# vmuzero_SEPS525_V2.net
KiCad netlist of a schematic drawn in EAGLE
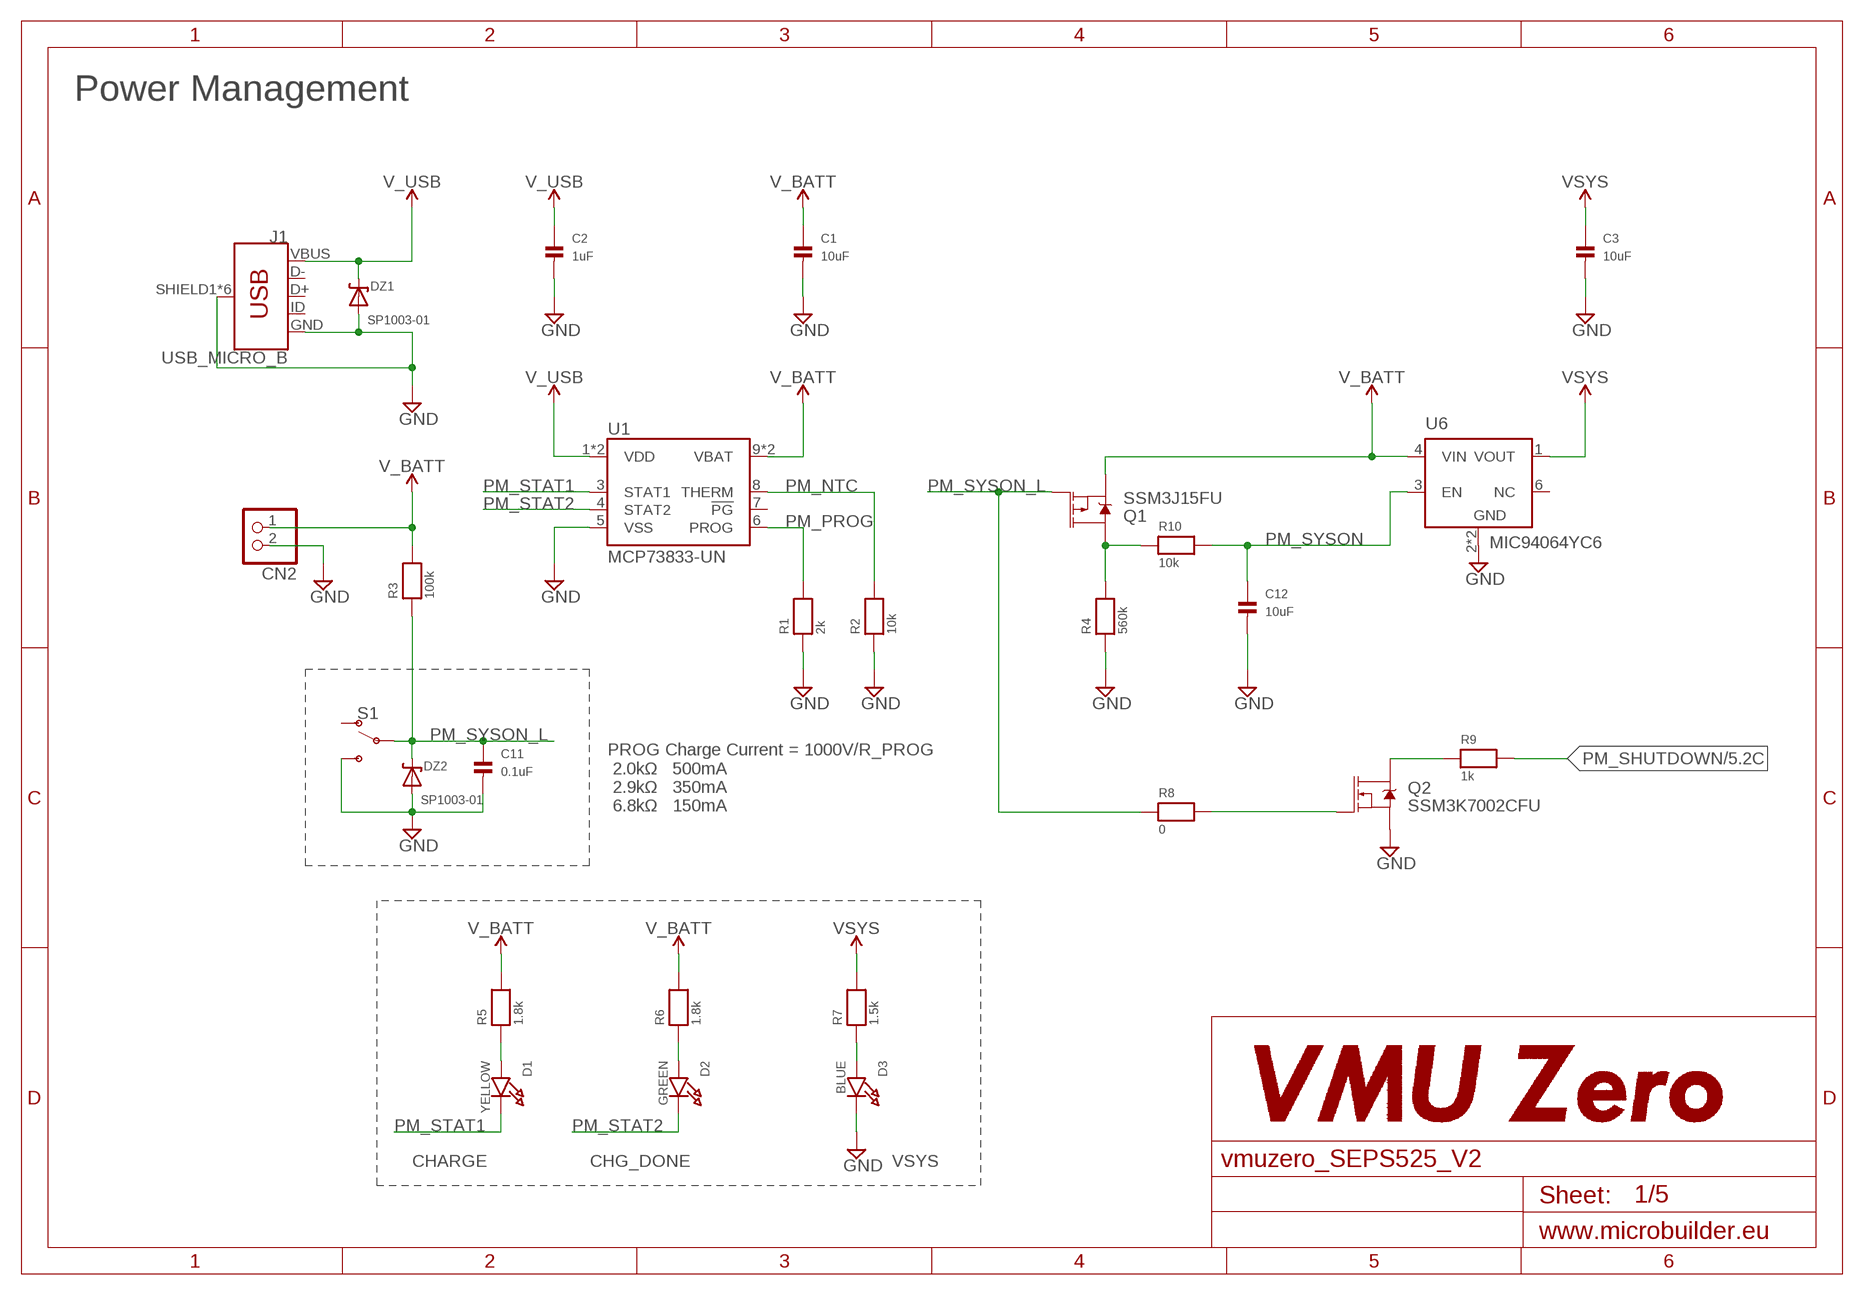
[diagram p0: schematic, sheet 1]
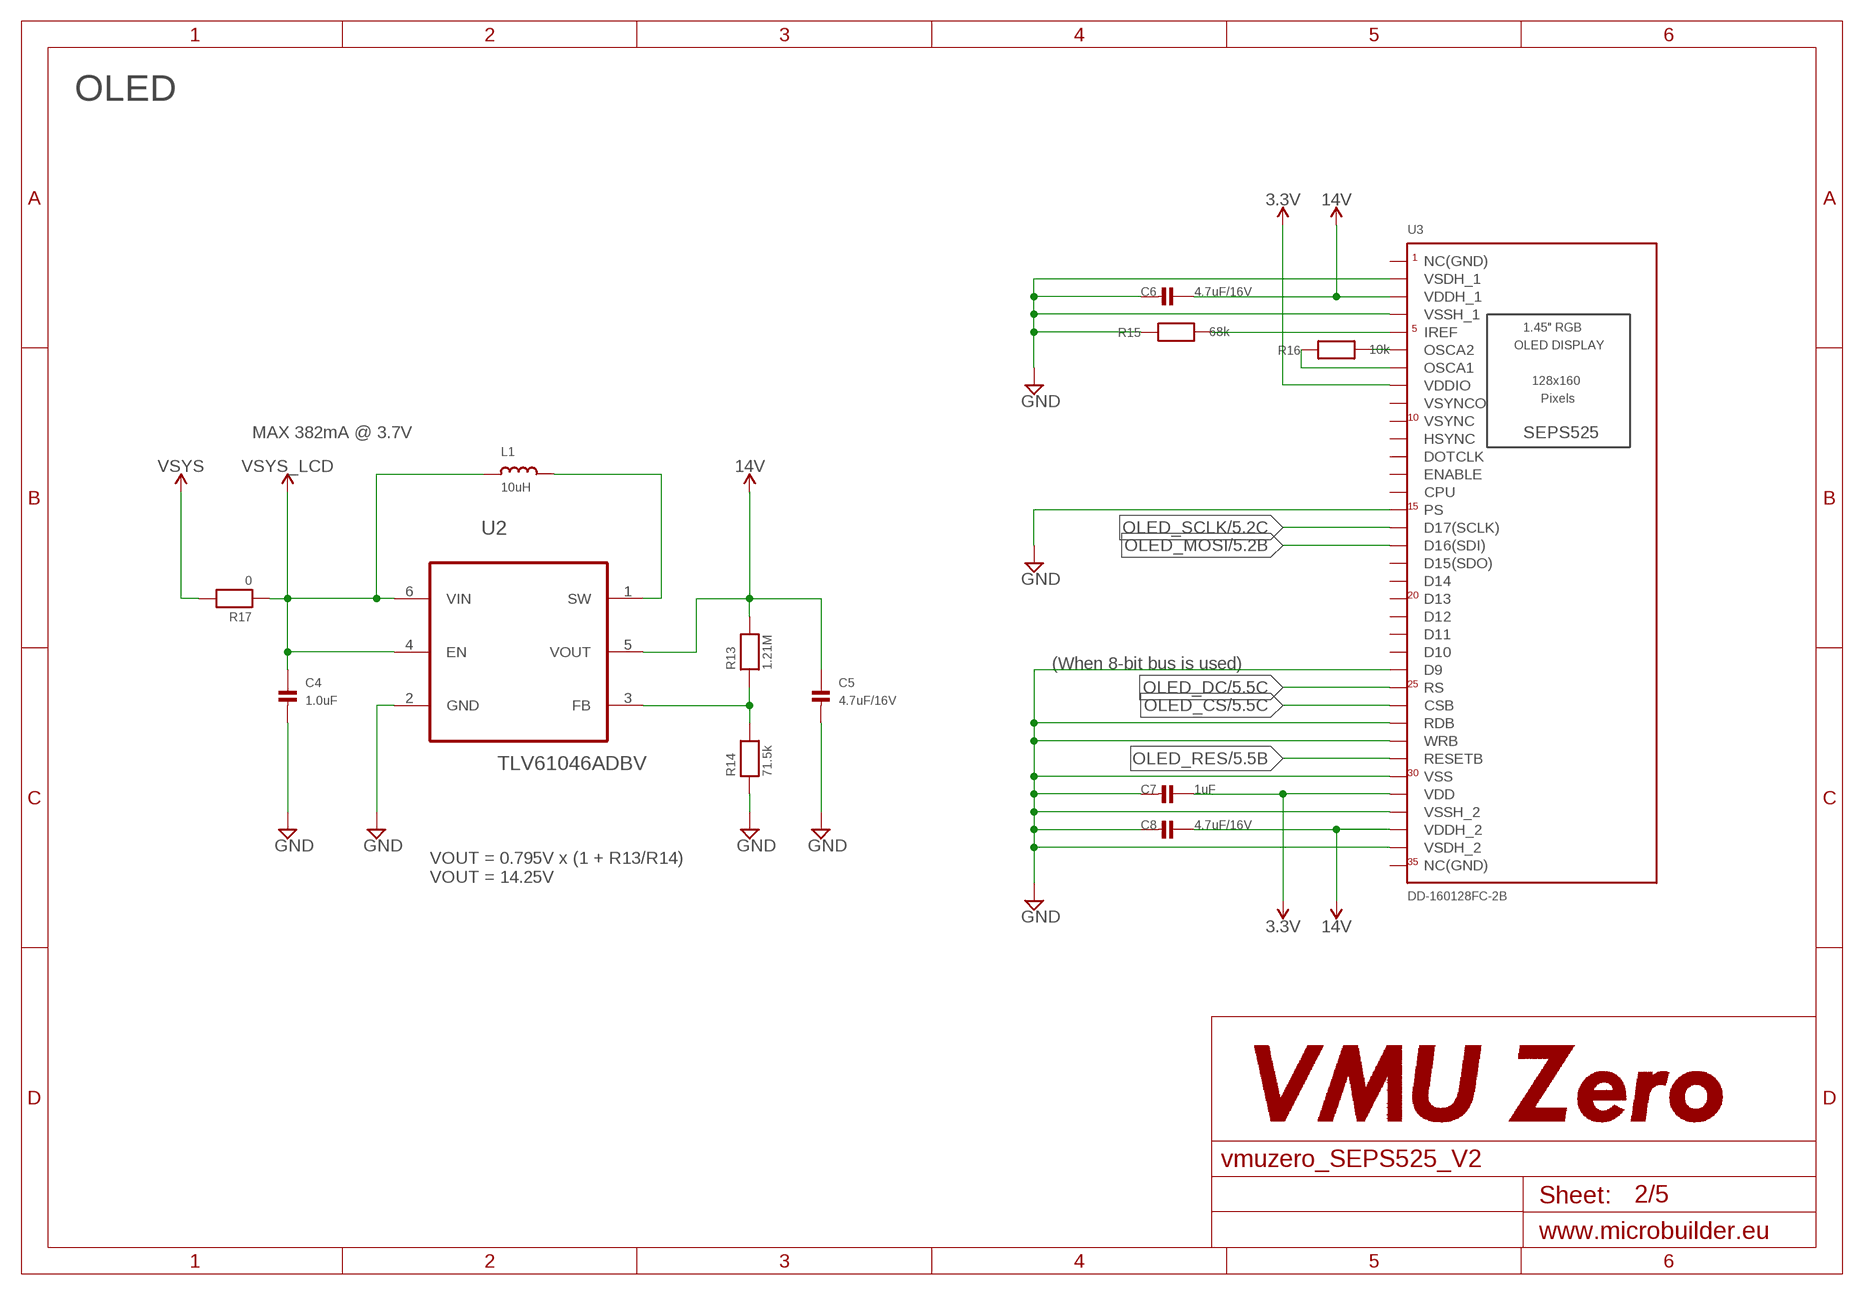
[diagram p1: schematic, sheet 2]
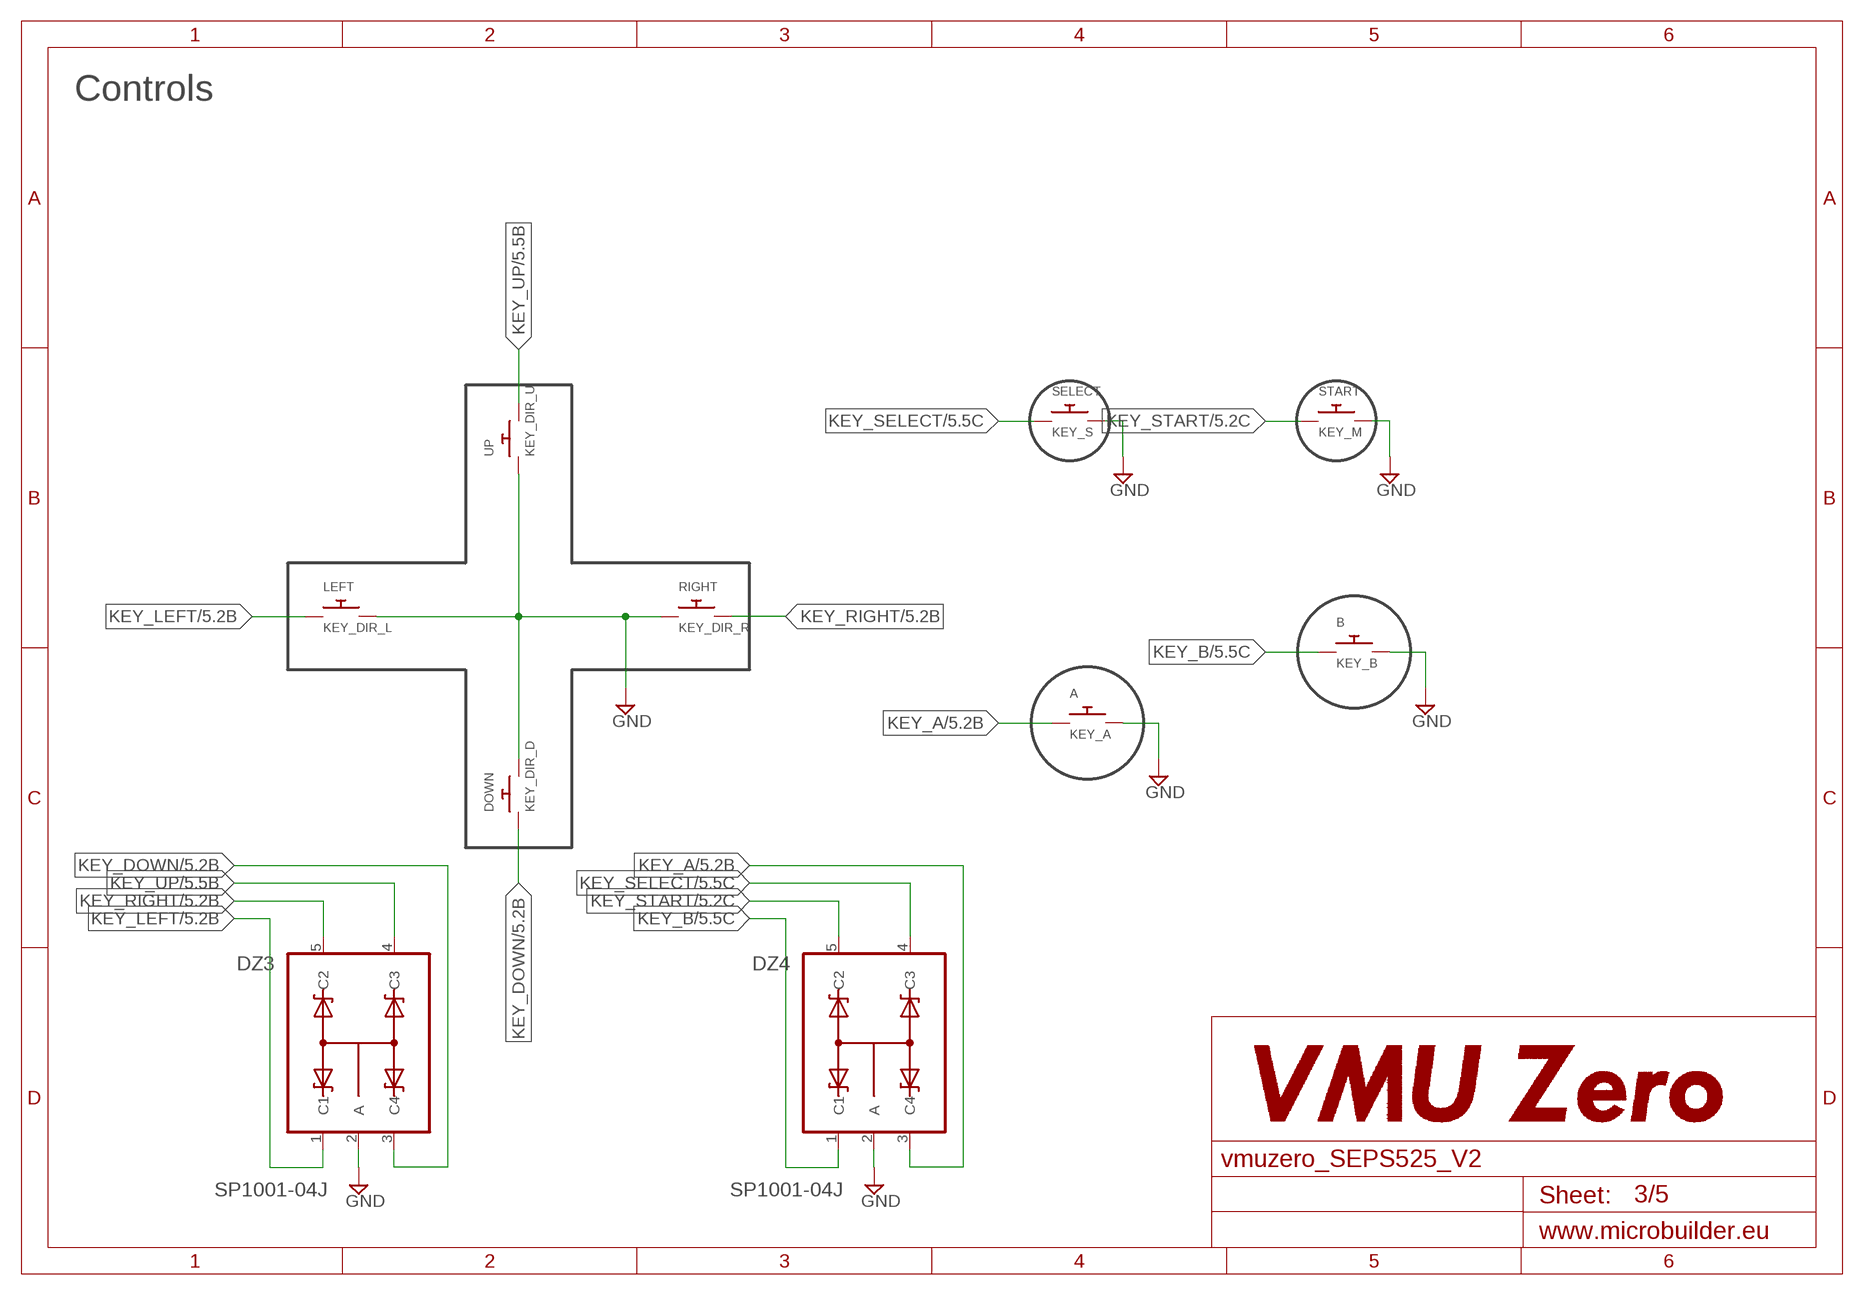
[diagram p2: schematic, sheet 3]
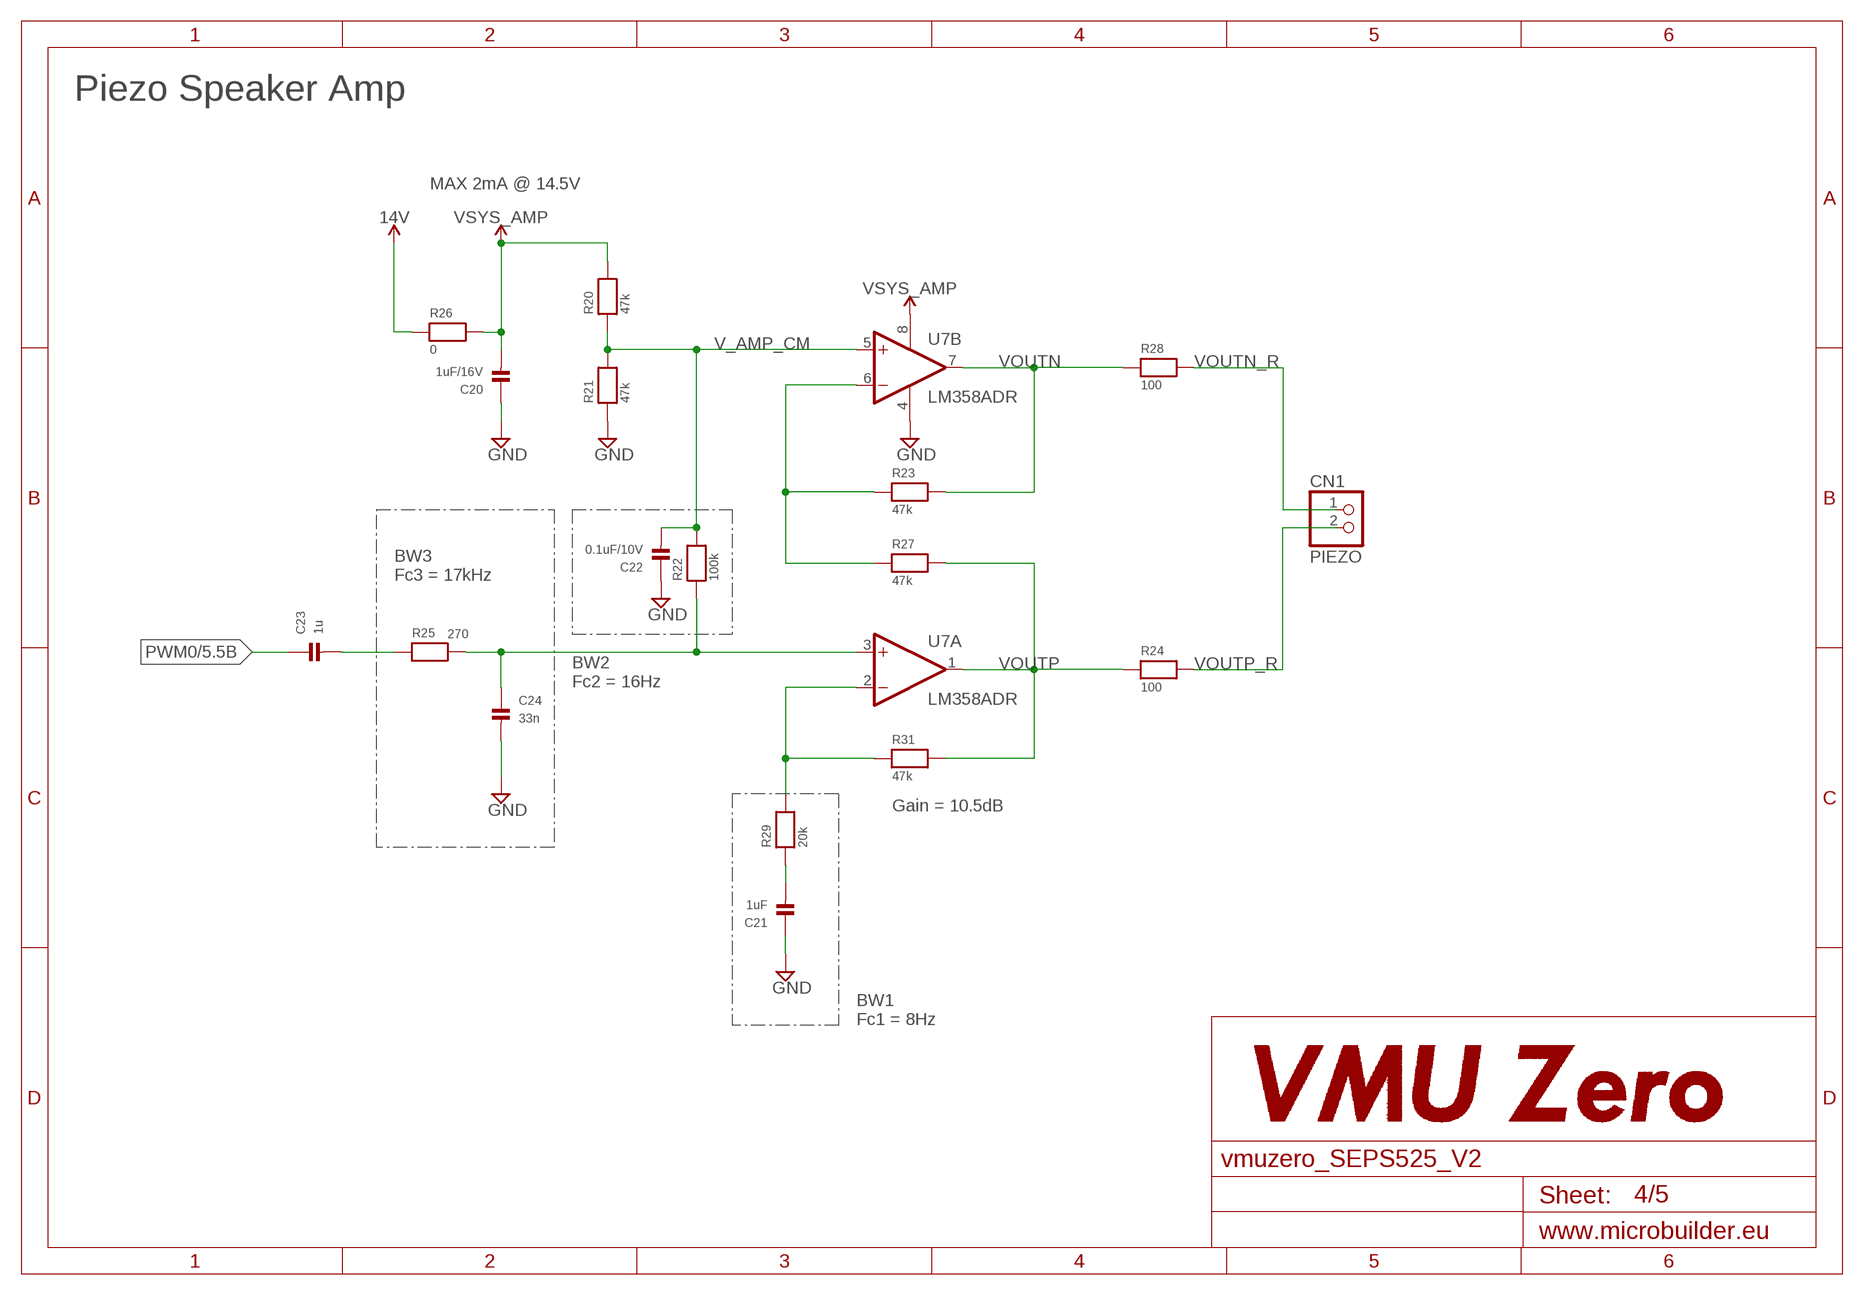
[diagram p3: schematic, sheet 4]
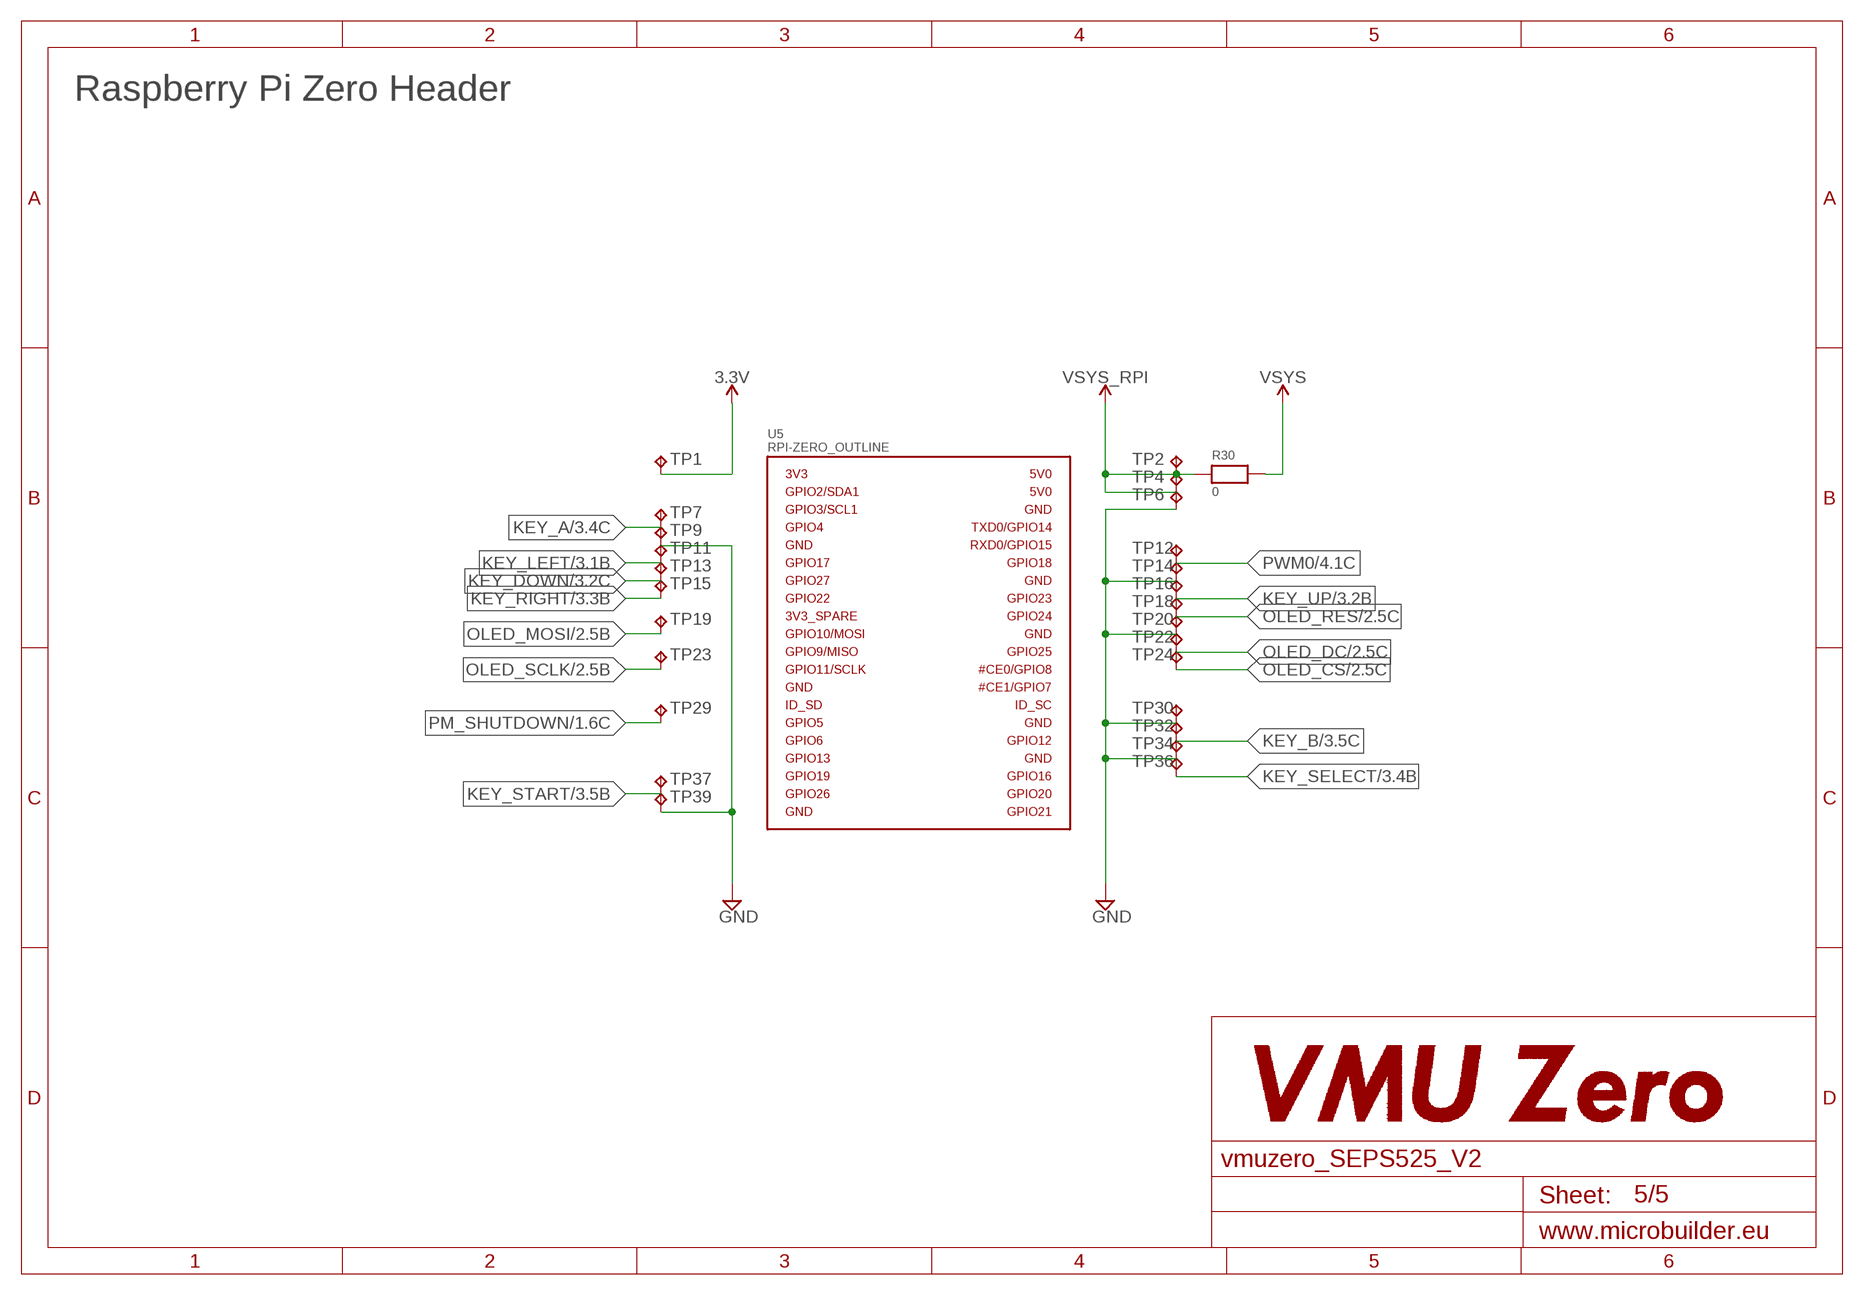
[diagram p4: schematic, sheet 5]

(export (version "E")
  (design (tool "Eeschema 10.0.6"))
  (components
    (comp (ref "C4")
      (value "1.0uF")
      (footprint "eagle-import:_0805MP")
      (libsource (lib "eagle-import") (part "CAP_CERAMIC_0805MP"))
    )
    (comp (ref "C5")
      (value "4.7uF/16V")
      (footprint "eagle-import:_0805MP")
      (libsource (lib "eagle-import") (part "CAP_CERAMIC_0805MP"))
    )
    (comp (ref "C6")
      (value "4.7uF/16V")
      (footprint "eagle-import:_0805MP")
      (libsource (lib "eagle-import") (part "CAP_CERAMIC_0805MP"))
    )
    (comp (ref "C7")
      (value "1uF")
      (footprint "eagle-import:_0805MP")
      (libsource (lib "eagle-import") (part "CAP_CERAMIC_0805MP"))
    )
    (comp (ref "C8")
      (value "4.7uF/16V")
      (footprint "eagle-import:_0805MP")
      (libsource (lib "eagle-import") (part "CAP_CERAMIC_0805MP"))
    )
    (comp (ref "L1")
      (value "10uH")
      (footprint "eagle-import:CIG22L")
      (libsource (lib "eagle-import") (part "INDUCTOR_CIG22L"))
    )
    (comp (ref "R13")
      (value "1.21M")
      (footprint "eagle-import:_0805MP")
      (libsource (lib "eagle-import") (part "RESISTOR_0805MP"))
    )
    (comp (ref "R14")
      (value "71.5k")
      (footprint "eagle-import:_0805MP")
      (libsource (lib "eagle-import") (part "RESISTOR_0805MP"))
    )
    (comp (ref "R15")
      (value "68k")
      (footprint "eagle-import:_0805MP")
      (libsource (lib "eagle-import") (part "RESISTOR_0805MP"))
    )
    (comp (ref "R16")
      (value "10k")
      (footprint "eagle-import:_0805MP")
      (libsource (lib "eagle-import") (part "RESISTOR_0805MP"))
    )
    (comp (ref "R17")
      (value "0")
      (footprint "eagle-import:_0805MP")
      (libsource (lib "eagle-import") (part "RESISTOR_0805MP"))
    )
    (comp (ref "U2")
      (value "TLV61046ADBV")
      (footprint "eagle-import:R-PDSO-G6")
      (libsource (lib "eagle-import") (part "TLV61046ADBV"))
    )
    (comp (ref "U3")
      (value "DD-160128FC-2B")
      (footprint "eagle-import:XF2M-3515-1A")
      (fields (field (name "MPN") "XF2M-3515-1A"))
      (libsource (lib "eagle-import") (part "DISP_OLED_DD-160128FC-2BNOSWAP"))
    )
    (comp (ref "A")
      (value "KEY_A")
      (footprint "eagle-import:KEYPAD_VMU_R26")
      (libsource (lib "eagle-import") (part "SWITCH_PUSH_VMU"))
    )
    (comp (ref "B")
      (value "KEY_B")
      (footprint "eagle-import:KEYPAD_VMU_R26")
      (libsource (lib "eagle-import") (part "SWITCH_PUSH_VMU"))
    )
    (comp (ref "DOWN")
      (value "KEY_DIR_D")
      (footprint "eagle-import:KEYPAD_VMU_R26")
      (libsource (lib "eagle-import") (part "SWITCH_PUSH_VMU"))
    )
    (comp (ref "DZ3")
      (value "SP1001-04J")
      (footprint "eagle-import:SC70-5")
      (fields (field (name "MPN") "SP1001-04"))
      (libsource (lib "eagle-import") (part "SP1001-04J"))
    )
    (comp (ref "DZ4")
      (value "SP1001-04J")
      (footprint "eagle-import:SC70-5")
      (fields (field (name "MPN") "SP1001-04"))
      (libsource (lib "eagle-import") (part "SP1001-04J"))
    )
    (comp (ref "LEFT")
      (value "KEY_DIR_L")
      (footprint "eagle-import:KEYPAD_VMU_R26")
      (libsource (lib "eagle-import") (part "SWITCH_PUSH_VMU"))
    )
    (comp (ref "RIGHT")
      (value "KEY_DIR_R")
      (footprint "eagle-import:KEYPAD_VMU_R26")
      (libsource (lib "eagle-import") (part "SWITCH_PUSH_VMU"))
    )
    (comp (ref "SELECT")
      (value "KEY_S")
      (footprint "eagle-import:KEYPAD_VMU_R26")
      (libsource (lib "eagle-import") (part "SWITCH_PUSH_VMU"))
    )
    (comp (ref "START")
      (value "KEY_M")
      (footprint "eagle-import:KEYPAD_VMU_R26")
      (libsource (lib "eagle-import") (part "SWITCH_PUSH_VMU"))
    )
    (comp (ref "UP")
      (value "KEY_DIR_U")
      (footprint "eagle-import:KEYPAD_VMU_R26")
      (libsource (lib "eagle-import") (part "SWITCH_PUSH_VMU"))
    )
    (comp (ref "C20")
      (value "1uF/16V")
      (footprint "eagle-import:_0805MP")
      (libsource (lib "eagle-import") (part "CAP_CERAMIC_0805MP"))
    )
    (comp (ref "C21")
      (value "1uF")
      (footprint "eagle-import:_0805MP")
      (libsource (lib "eagle-import") (part "CAP_CERAMIC_0805MP"))
    )
    (comp (ref "C22")
      (value "0.1uF/10V")
      (footprint "eagle-import:_0805MP")
      (libsource (lib "eagle-import") (part "CAP_CERAMIC_0805MP"))
    )
    (comp (ref "C23")
      (value "1u")
      (footprint "eagle-import:_0805MP")
      (libsource (lib "eagle-import") (part "CAP_CERAMIC_0805MP"))
    )
    (comp (ref "C24")
      (value "33n")
      (footprint "eagle-import:_0805MP")
      (libsource (lib "eagle-import") (part "CAP_CERAMIC_0805MP"))
    )
    (comp (ref "CN1")
      (value "PIEZO")
      (footprint "eagle-import:1X02_ROUND")
      (libsource (lib "eagle-import") (part "HEADER-1X2ROUND"))
    )
    (comp (ref "R20")
      (value "47k")
      (footprint "eagle-import:_0805MP")
      (libsource (lib "eagle-import") (part "RESISTOR_0805MP"))
    )
    (comp (ref "R21")
      (value "47k")
      (footprint "eagle-import:_0805MP")
      (libsource (lib "eagle-import") (part "RESISTOR_0805MP"))
    )
    (comp (ref "R22")
      (value "100k")
      (footprint "eagle-import:_0805MP")
      (libsource (lib "eagle-import") (part "RESISTOR_0805MP"))
    )
    (comp (ref "R23")
      (value "47k")
      (footprint "eagle-import:_0805MP")
      (libsource (lib "eagle-import") (part "RESISTOR_0805MP"))
    )
    (comp (ref "R24")
      (value "100")
      (footprint "eagle-import:_0805MP")
      (libsource (lib "eagle-import") (part "RESISTOR_0805MP"))
    )
    (comp (ref "R25")
      (value "270")
      (footprint "eagle-import:_0805MP")
      (libsource (lib "eagle-import") (part "RESISTOR_0805MP"))
    )
    (comp (ref "R26")
      (value "0")
      (footprint "eagle-import:_0805MP")
      (libsource (lib "eagle-import") (part "RESISTOR_0805MP"))
    )
    (comp (ref "R27")
      (value "47k")
      (footprint "eagle-import:_0805MP")
      (libsource (lib "eagle-import") (part "RESISTOR_0805MP"))
    )
    (comp (ref "R28")
      (value "100")
      (footprint "eagle-import:_0805MP")
      (libsource (lib "eagle-import") (part "RESISTOR_0805MP"))
    )
    (comp (ref "R29")
      (value "20k")
      (footprint "eagle-import:_0805MP")
      (libsource (lib "eagle-import") (part "RESISTOR_0805MP"))
    )
    (comp (ref "R31")
      (value "47k")
      (footprint "eagle-import:_0805MP")
      (libsource (lib "eagle-import") (part "RESISTOR_0805MP"))
    )
    (comp (ref "U7")
      (value "LM358ADR")
      (footprint "eagle-import:SO08")
      (libsource (lib "eagle-import") (part "LM358ADR"))
    )
    (comp (ref "R30")
      (value "0")
      (footprint "eagle-import:_0805MP")
      (libsource (lib "eagle-import") (part "RESISTOR_0805MP"))
    )
    (comp (ref "TP1")
      (value "TPTP14SQ")
      (footprint "eagle-import:TP14SQ")
      (libsource (lib "eagle-import") (part "TPTP14SQ"))
    )
    (comp (ref "TP2")
      (value "TPTP14R")
      (footprint "eagle-import:TP14R")
      (libsource (lib "eagle-import") (part "TPTP14R"))
    )
    (comp (ref "TP4")
      (value "TPTP14R")
      (footprint "eagle-import:TP14R")
      (libsource (lib "eagle-import") (part "TPTP14R"))
    )
    (comp (ref "TP6")
      (value "TPTP14R")
      (footprint "eagle-import:TP14R")
      (libsource (lib "eagle-import") (part "TPTP14R"))
    )
    (comp (ref "TP7")
      (value "TPTP14R")
      (footprint "eagle-import:TP14R")
      (libsource (lib "eagle-import") (part "TPTP14R"))
    )
    (comp (ref "TP9")
      (value "TPTP14R")
      (footprint "eagle-import:TP14R")
      (libsource (lib "eagle-import") (part "TPTP14R"))
    )
    (comp (ref "TP11")
      (value "TPTP14R")
      (footprint "eagle-import:TP14R")
      (libsource (lib "eagle-import") (part "TPTP14R"))
    )
    (comp (ref "TP12")
      (value "TPTP14R")
      (footprint "eagle-import:TP14R")
      (libsource (lib "eagle-import") (part "TPTP14R"))
    )
    (comp (ref "TP13")
      (value "TPTP14R")
      (footprint "eagle-import:TP14R")
      (libsource (lib "eagle-import") (part "TPTP14R"))
    )
    (comp (ref "TP14")
      (value "TPTP14R")
      (footprint "eagle-import:TP14R")
      (libsource (lib "eagle-import") (part "TPTP14R"))
    )
    (comp (ref "TP15")
      (value "TPTP14R")
      (footprint "eagle-import:TP14R")
      (libsource (lib "eagle-import") (part "TPTP14R"))
    )
    (comp (ref "TP16")
      (value "TPTP14R")
      (footprint "eagle-import:TP14R")
      (libsource (lib "eagle-import") (part "TPTP14R"))
    )
    (comp (ref "TP18")
      (value "TPTP14R")
      (footprint "eagle-import:TP14R")
      (libsource (lib "eagle-import") (part "TPTP14R"))
    )
    (comp (ref "TP19")
      (value "TPTP14R")
      (footprint "eagle-import:TP14R")
      (libsource (lib "eagle-import") (part "TPTP14R"))
    )
    (comp (ref "TP20")
      (value "TPTP14R")
      (footprint "eagle-import:TP14R")
      (libsource (lib "eagle-import") (part "TPTP14R"))
    )
    (comp (ref "TP22")
      (value "TPTP14R")
      (footprint "eagle-import:TP14R")
      (libsource (lib "eagle-import") (part "TPTP14R"))
    )
    (comp (ref "TP23")
      (value "TPTP14R")
      (footprint "eagle-import:TP14R")
      (libsource (lib "eagle-import") (part "TPTP14R"))
    )
    (comp (ref "TP24")
      (value "TPTP14R")
      (footprint "eagle-import:TP14R")
      (libsource (lib "eagle-import") (part "TPTP14R"))
    )
    (comp (ref "TP29")
      (value "TPTP14R")
      (footprint "eagle-import:TP14R")
      (libsource (lib "eagle-import") (part "TPTP14R"))
    )
    (comp (ref "TP30")
      (value "TPTP14R")
      (footprint "eagle-import:TP14R")
      (libsource (lib "eagle-import") (part "TPTP14R"))
    )
    (comp (ref "TP32")
      (value "TPTP14R")
      (footprint "eagle-import:TP14R")
      (libsource (lib "eagle-import") (part "TPTP14R"))
    )
    (comp (ref "TP34")
      (value "TPTP14R")
      (footprint "eagle-import:TP14R")
      (libsource (lib "eagle-import") (part "TPTP14R"))
    )
    (comp (ref "TP36")
      (value "TPTP14R")
      (footprint "eagle-import:TP14R")
      (libsource (lib "eagle-import") (part "TPTP14R"))
    )
    (comp (ref "TP37")
      (value "TPTP14R")
      (footprint "eagle-import:TP14R")
      (libsource (lib "eagle-import") (part "TPTP14R"))
    )
    (comp (ref "TP39")
      (value "TPTP14R")
      (footprint "eagle-import:TP14R")
      (libsource (lib "eagle-import") (part "TPTP14R"))
    )
    (comp (ref "U5")
      (value "RPI-ZERO_OUTLINE")
      (footprint "eagle-import:RASP_PI_ZERO_OUTLINE_SMD")
      (libsource (lib "eagle-import") (part "RPI-ZERO_OUTLINE"))
    )
    (comp (ref "C1")
      (value "10uF")
      (footprint "eagle-import:_0805MP")
      (libsource (lib "eagle-import") (part "CAP_CERAMIC_0805MP"))
    )
    (comp (ref "C2")
      (value "1uF")
      (footprint "eagle-import:_0805MP")
      (libsource (lib "eagle-import") (part "CAP_CERAMIC_0805MP"))
    )
    (comp (ref "C3")
      (value "10uF")
      (footprint "eagle-import:_0805MP")
      (libsource (lib "eagle-import") (part "CAP_CERAMIC_0805MP"))
    )
    (comp (ref "C11")
      (value "0.1uF")
      (footprint "eagle-import:_0805MP")
      (libsource (lib "eagle-import") (part "CAP_CERAMIC_0805MP"))
    )
    (comp (ref "C12")
      (value "10uF")
      (footprint "eagle-import:_0805MP")
      (libsource (lib "eagle-import") (part "CAP_CERAMIC_0805MP"))
    )
    (comp (ref "CN2")
      (value "JST_2PIN")
      (footprint "eagle-import:S2B-PH-K-S")
      (libsource (lib "eagle-import") (part "JST_2PIN"))
    )
    (comp (ref "D1")
      (value "YELLOW")
      (footprint "eagle-import:CHIPLED_0805_NOOUTLINE")
      (libsource (lib "eagle-import") (part "LED0805_NOOUTLINE"))
    )
    (comp (ref "D2")
      (value "GREEN")
      (footprint "eagle-import:CHIPLED_0805_NOOUTLINE")
      (libsource (lib "eagle-import") (part "LED0805_NOOUTLINE"))
    )
    (comp (ref "D3")
      (value "BLUE")
      (footprint "eagle-import:CHIPLED_0805_NOOUTLINE")
      (libsource (lib "eagle-import") (part "LED0805_NOOUTLINE"))
    )
    (comp (ref "DZ1")
      (value "SP1003-01")
      (footprint "eagle-import:DIODE_SOD723")
      (libsource (lib "eagle-import") (part "SP1003-01D"))
    )
    (comp (ref "DZ2")
      (value "SP1003-01")
      (footprint "eagle-import:DIODE_SOD723")
      (libsource (lib "eagle-import") (part "SP1003-01D"))
    )
    (comp (ref "J1")
      (value "USB_MICRO_B")
      (footprint "eagle-import:USB-MICROB_10118192")
      (fields (field (name "MPN") "10118192-0001LF‎"))
      (libsource (lib "eagle-import") (part "USB_MICRO-B_AMP_10118192"))
    )
    (comp (ref "Q1")
      (value "SSM3J15FU")
      (footprint "eagle-import:SOT323")
      (fields (field (name "MANUFACTURER") "Toshiba"))
      (libsource (lib "eagle-import") (part "MOSFET_PCH-SSM3J15FU"))
    )
    (comp (ref "Q2")
      (value "SSM3K7002CFU")
      (footprint "eagle-import:SOT323")
      (fields (field (name "MANUFACTURER") "Toshiba"))
      (libsource (lib "eagle-import") (part "MOSFET_NCH-SSM3K7002CFU"))
    )
    (comp (ref "R1")
      (value "2k")
      (footprint "eagle-import:_0805MP")
      (libsource (lib "eagle-import") (part "RESISTOR_0805MP"))
    )
    (comp (ref "R2")
      (value "10k")
      (footprint "eagle-import:_0805MP")
      (libsource (lib "eagle-import") (part "RESISTOR_0805MP"))
    )
    (comp (ref "R3")
      (value "100k")
      (footprint "eagle-import:_0805MP")
      (libsource (lib "eagle-import") (part "RESISTOR_0805MP"))
    )
    (comp (ref "R4")
      (value "560k")
      (footprint "eagle-import:_0805MP")
      (libsource (lib "eagle-import") (part "RESISTOR_0805MP"))
    )
    (comp (ref "R5")
      (value "1.8k")
      (footprint "eagle-import:_0805MP")
      (libsource (lib "eagle-import") (part "RESISTOR_0805MP"))
    )
    (comp (ref "R6")
      (value "1.8k")
      (footprint "eagle-import:_0805MP")
      (libsource (lib "eagle-import") (part "RESISTOR_0805MP"))
    )
    (comp (ref "R7")
      (value "1.5k")
      (footprint "eagle-import:_0805MP")
      (libsource (lib "eagle-import") (part "RESISTOR_0805MP"))
    )
    (comp (ref "R8")
      (value "0")
      (footprint "eagle-import:_0805MP")
      (libsource (lib "eagle-import") (part "RESISTOR_0805MP"))
    )
    (comp (ref "R9")
      (value "1k")
      (footprint "eagle-import:_0805MP")
      (libsource (lib "eagle-import") (part "RESISTOR_0805MP"))
    )
    (comp (ref "R10")
      (value "10k")
      (footprint "eagle-import:_0805MP")
      (libsource (lib "eagle-import") (part "RESISTOR_0805MP"))
    )
    (comp (ref "S1")
      (value "SWITCH-SPDT")
      (footprint "eagle-import:SPDT_JS102011SAQN")
      (fields (field (name "MPN") "JS102011SAQN"))
      (libsource (lib "eagle-import") (part "SWITCH-SPDT"))
    )
    (comp (ref "U1")
      (value "MCP73833-UN")
      (footprint "eagle-import:10L_MSOP")
      (libsource (lib "eagle-import") (part "MCP73833-UN"))
    )
    (comp (ref "U6")
      (value "MIC94064YC6")
      (footprint "eagle-import:SC70-6L")
      (libsource (lib "eagle-import") (part "MIC94064YC6"))
    )
  )
  (nets
    (net (code "1") (name "3.3V") (class "Default")
      (node (ref "C7") (pin "1") (pinfunction "P$1_1") (pintype "passive"))
      (node (ref "TP1") (pin "TP") (pinfunction "TP_TP") (pintype "input"))
      (node (ref "U3") (pin "31") (pinfunction "VDD_31") (pintype "power_in"))
      (node (ref "U3") (pin "8") (pinfunction "VDDIO_8") (pintype "power_in"))
    )
    (net (code "2") (name "14V") (class "Default")
      (node (ref "C5") (pin "1") (pinfunction "P$1_1") (pintype "passive"))
      (node (ref "C6") (pin "1") (pinfunction "P$1_1") (pintype "passive"))
      (node (ref "C8") (pin "1") (pinfunction "P$1_1") (pintype "passive"))
      (node (ref "R13") (pin "2") (pinfunction "2_2") (pintype "passive"))
      (node (ref "R26") (pin "1") (pinfunction "1_1") (pintype "passive"))
      (node (ref "U2") (pin "5") (pinfunction "VOUT_5") (pintype "passive"))
      (node (ref "U3") (pin "3") (pinfunction "VDDH_1_3") (pintype "power_in"))
      (node (ref "U3") (pin "33") (pinfunction "VDDH_2_33") (pintype "power_in"))
    )
    (net (code "3") (name "GND") (class "Default")
      (node (ref "A") (pin "2") (pinfunction "P$2_2") (pintype "passive"))
      (node (ref "B") (pin "2") (pinfunction "P$2_2") (pintype "passive"))
      (node (ref "C1") (pin "2") (pinfunction "P$2_2") (pintype "passive"))
      (node (ref "C11") (pin "2") (pinfunction "P$2_2") (pintype "passive"))
      (node (ref "C12") (pin "2") (pinfunction "P$2_2") (pintype "passive"))
      (node (ref "C2") (pin "2") (pinfunction "P$2_2") (pintype "passive"))
      (node (ref "C20") (pin "1") (pinfunction "P$1_1") (pintype "passive"))
      (node (ref "C21") (pin "1") (pinfunction "P$1_1") (pintype "passive"))
      (node (ref "C22") (pin "1") (pinfunction "P$1_1") (pintype "passive"))
      (node (ref "C24") (pin "2") (pinfunction "P$2_2") (pintype "passive"))
      (node (ref "C3") (pin "2") (pinfunction "P$2_2") (pintype "passive"))
      (node (ref "C4") (pin "2") (pinfunction "P$2_2") (pintype "passive"))
      (node (ref "C5") (pin "2") (pinfunction "P$2_2") (pintype "passive"))
      (node (ref "C6") (pin "2") (pinfunction "P$2_2") (pintype "passive"))
      (node (ref "C7") (pin "2") (pinfunction "P$2_2") (pintype "passive"))
      (node (ref "C8") (pin "2") (pinfunction "P$2_2") (pintype "passive"))
      (node (ref "CN2") (pin "2") (pinfunction "1_2") (pintype "passive"))
      (node (ref "D3") (pin "C") (pinfunction "C_C") (pintype "passive"))
      (node (ref "DOWN") (pin "2") (pinfunction "P$2_2") (pintype "passive"))
      (node (ref "DZ1") (pin "A") (pinfunction "A_A") (pintype "passive"))
      (node (ref "DZ2") (pin "A") (pinfunction "A_A") (pintype "passive"))
      (node (ref "DZ3") (pin "2") (pinfunction "A_2") (pintype "passive"))
      (node (ref "DZ4") (pin "2") (pinfunction "A_2") (pintype "passive"))
      (node (ref "J1") (pin "GND") (pinfunction "GND_GND") (pintype "power_in"))
      (node (ref "J1") (pin "SHIELD1") (pinfunction "SHIELD_SHIELD1") (pintype "bidirectional"))
      (node (ref "J1") (pin "SHIELD2") (pinfunction "SHIELD_SHIELD2") (pintype "bidirectional"))
      (node (ref "J1") (pin "SHIELD3") (pinfunction "SHIELD_SHIELD3") (pintype "bidirectional"))
      (node (ref "J1") (pin "SHIELD4") (pinfunction "SHIELD_SHIELD4") (pintype "bidirectional"))
      (node (ref "J1") (pin "SHIELD5") (pinfunction "SHIELD_SHIELD5") (pintype "bidirectional"))
      (node (ref "J1") (pin "SHIELD6") (pinfunction "SHIELD_SHIELD6") (pintype "bidirectional"))
      (node (ref "LEFT") (pin "2") (pinfunction "P$2_2") (pintype "passive"))
      (node (ref "Q2") (pin "2") (pinfunction "S_2") (pintype "bidirectional"))
      (node (ref "R1") (pin "1") (pinfunction "1_1") (pintype "passive"))
      (node (ref "R14") (pin "1") (pinfunction "1_1") (pintype "passive"))
      (node (ref "R15") (pin "2") (pinfunction "2_2") (pintype "passive"))
      (node (ref "R2") (pin "1") (pinfunction "1_1") (pintype "passive"))
      (node (ref "R21") (pin "1") (pinfunction "1_1") (pintype "passive"))
      (node (ref "R4") (pin "1") (pinfunction "1_1") (pintype "passive"))
      (node (ref "RIGHT") (pin "1") (pinfunction "P$1_1") (pintype "passive"))
      (node (ref "S1") (pin "P$3") (pinfunction "S_P$3") (pintype "passive"))
      (node (ref "SELECT") (pin "2") (pinfunction "P$2_2") (pintype "passive"))
      (node (ref "START") (pin "2") (pinfunction "P$2_2") (pintype "passive"))
      (node (ref "TP14") (pin "TP") (pinfunction "TP_TP") (pintype "input"))
      (node (ref "TP20") (pin "TP") (pinfunction "TP_TP") (pintype "input"))
      (node (ref "TP30") (pin "TP") (pinfunction "TP_TP") (pintype "input"))
      (node (ref "TP34") (pin "TP") (pinfunction "TP_TP") (pintype "input"))
      (node (ref "TP39") (pin "TP") (pinfunction "TP_TP") (pintype "input"))
      (node (ref "TP6") (pin "TP") (pinfunction "TP_TP") (pintype "input"))
      (node (ref "TP9") (pin "TP") (pinfunction "TP_TP") (pintype "input"))
      (node (ref "U1") (pin "5") (pinfunction "VSS_5") (pintype "power_in"))
      (node (ref "U2") (pin "2") (pinfunction "GND_2") (pintype "passive"))
      (node (ref "U3") (pin "15") (pinfunction "PS_15") (pintype "bidirectional"))
      (node (ref "U3") (pin "2") (pinfunction "VSDH_1_2") (pintype "passive"))
      (node (ref "U3") (pin "24") (pinfunction "D9_24") (pintype "bidirectional"))
      (node (ref "U3") (pin "27") (pinfunction "RDB_27") (pintype "bidirectional"))
      (node (ref "U3") (pin "28") (pinfunction "WRB_28") (pintype "bidirectional"))
      (node (ref "U3") (pin "30") (pinfunction "VSS_30") (pintype "passive"))
      (node (ref "U3") (pin "32") (pinfunction "VSSH_2_32") (pintype "passive"))
      (node (ref "U3") (pin "34") (pinfunction "VSDH_2_34") (pintype "passive"))
      (node (ref "U3") (pin "4") (pinfunction "VSSH_1_4") (pintype "passive"))
      (node (ref "U6") (pin "2") (pinfunction "GND_2") (pintype "power_in"))
      (node (ref "U6") (pin "5") (pinfunction "GND_5") (pintype "power_in"))
      (node (ref "U7") (pin "4") (pinfunction "V-_4") (pintype "power_in"))
      (node (ref "UP") (pin "1") (pinfunction "P$1_1") (pintype "passive"))
    )
    (net (code "4") (name "KEY_A") (class "Default")
      (node (ref "A") (pin "1") (pinfunction "P$1_1") (pintype "passive"))
      (node (ref "DZ4") (pin "3") (pinfunction "C4_3") (pintype "passive"))
      (node (ref "TP7") (pin "TP") (pinfunction "TP_TP") (pintype "input"))
    )
    (net (code "5") (name "KEY_B") (class "Default")
      (node (ref "B") (pin "1") (pinfunction "P$1_1") (pintype "passive"))
      (node (ref "DZ4") (pin "1") (pinfunction "C1_1") (pintype "passive"))
      (node (ref "TP32") (pin "TP") (pinfunction "TP_TP") (pintype "input"))
    )
    (net (code "6") (name "KEY_DOWN") (class "Default")
      (node (ref "DOWN") (pin "1") (pinfunction "P$1_1") (pintype "passive"))
      (node (ref "DZ3") (pin "3") (pinfunction "C4_3") (pintype "passive"))
      (node (ref "TP13") (pin "TP") (pinfunction "TP_TP") (pintype "input"))
    )
    (net (code "7") (name "KEY_LEFT") (class "Default")
      (node (ref "DZ3") (pin "1") (pinfunction "C1_1") (pintype "passive"))
      (node (ref "LEFT") (pin "1") (pinfunction "P$1_1") (pintype "passive"))
      (node (ref "TP11") (pin "TP") (pinfunction "TP_TP") (pintype "input"))
    )
    (net (code "8") (name "KEY_RIGHT") (class "Default")
      (node (ref "DZ3") (pin "5") (pinfunction "C2_5") (pintype "passive"))
      (node (ref "RIGHT") (pin "2") (pinfunction "P$2_2") (pintype "passive"))
      (node (ref "TP15") (pin "TP") (pinfunction "TP_TP") (pintype "input"))
    )
    (net (code "9") (name "KEY_SELECT") (class "Default")
      (node (ref "DZ4") (pin "4") (pinfunction "C3_4") (pintype "passive"))
      (node (ref "SELECT") (pin "1") (pinfunction "P$1_1") (pintype "passive"))
      (node (ref "TP36") (pin "TP") (pinfunction "TP_TP") (pintype "input"))
    )
    (net (code "10") (name "KEY_START") (class "Default")
      (node (ref "DZ4") (pin "5") (pinfunction "C2_5") (pintype "passive"))
      (node (ref "START") (pin "1") (pinfunction "P$1_1") (pintype "passive"))
      (node (ref "TP37") (pin "TP") (pinfunction "TP_TP") (pintype "input"))
    )
    (net (code "11") (name "KEY_UP") (class "Default")
      (node (ref "DZ3") (pin "4") (pinfunction "C3_4") (pintype "passive"))
      (node (ref "TP16") (pin "TP") (pinfunction "TP_TP") (pintype "input"))
      (node (ref "UP") (pin "2") (pinfunction "P$2_2") (pintype "passive"))
    )
    (net (code "12") (name "Net-(C21-P$2)") (class "Default")
      (node (ref "C21") (pin "2") (pinfunction "P$2_2") (pintype "passive"))
      (node (ref "R29") (pin "1") (pinfunction "1_1") (pintype "passive"))
    )
    (net (code "13") (name "Net-(C23-P$2)") (class "Default")
      (node (ref "C23") (pin "2") (pinfunction "P$2_2") (pintype "passive"))
      (node (ref "R25") (pin "1") (pinfunction "1_1") (pintype "passive"))
    )
    (net (code "14") (name "Net-(C24-P$1)") (class "Default")
      (node (ref "C24") (pin "1") (pinfunction "P$1_1") (pintype "passive"))
      (node (ref "R22") (pin "1") (pinfunction "1_1") (pintype "passive"))
      (node (ref "R25") (pin "2") (pinfunction "2_2") (pintype "passive"))
      (node (ref "U7") (pin "3") (pinfunction "+IN_3") (pintype "input"))
    )
    (net (code "15") (name "Net-(D1-PadA)") (class "Default")
      (node (ref "D1") (pin "A") (pinfunction "A_A") (pintype "passive"))
      (node (ref "R5") (pin "1") (pinfunction "1_1") (pintype "passive"))
    )
    (net (code "16") (name "Net-(D2-PadA)") (class "Default")
      (node (ref "D2") (pin "A") (pinfunction "A_A") (pintype "passive"))
      (node (ref "R6") (pin "1") (pinfunction "1_1") (pintype "passive"))
    )
    (net (code "17") (name "Net-(D3-PadA)") (class "Default")
      (node (ref "D3") (pin "A") (pinfunction "A_A") (pintype "passive"))
      (node (ref "R7") (pin "1") (pinfunction "1_1") (pintype "passive"))
    )
    (net (code "18") (name "Net-(L1-2)") (class "Default")
      (node (ref "L1") (pin "P$2") (pinfunction "2_P$2") (pintype "passive"))
      (node (ref "U2") (pin "1") (pinfunction "SW_1") (pintype "input"))
    )
    (net (code "19") (name "Net-(Q1-D)") (class "Default")
      (node (ref "Q1") (pin "3") (pinfunction "D_3") (pintype "bidirectional"))
      (node (ref "R10") (pin "1") (pinfunction "1_1") (pintype "passive"))
      (node (ref "R4") (pin "2") (pinfunction "2_2") (pintype "passive"))
    )
    (net (code "20") (name "Net-(Q2-D)") (class "Default")
      (node (ref "Q2") (pin "3") (pinfunction "D_3") (pintype "bidirectional"))
      (node (ref "R9") (pin "1") (pinfunction "1_1") (pintype "passive"))
    )
    (net (code "21") (name "Net-(Q2-G)") (class "Default")
      (node (ref "Q2") (pin "1") (pinfunction "G_1") (pintype "bidirectional"))
      (node (ref "R8") (pin "2") (pinfunction "2_2") (pintype "passive"))
    )
    (net (code "22") (name "Net-(U2-FB)") (class "Default")
      (node (ref "R13") (pin "1") (pinfunction "1_1") (pintype "passive"))
      (node (ref "R14") (pin "2") (pinfunction "2_2") (pintype "passive"))
      (node (ref "U2") (pin "3") (pinfunction "FB_3") (pintype "input"))
    )
    (net (code "23") (name "Net-(U3-IREF)") (class "Default")
      (node (ref "R15") (pin "1") (pinfunction "1_1") (pintype "passive"))
      (node (ref "U3") (pin "5") (pinfunction "IREF_5") (pintype "bidirectional"))
    )
    (net (code "24") (name "Net-(U3-OSCA1)") (class "Default")
      (node (ref "R16") (pin "2") (pinfunction "2_2") (pintype "passive"))
      (node (ref "U3") (pin "7") (pinfunction "OSCA1_7") (pintype "bidirectional"))
    )
    (net (code "25") (name "Net-(U3-OSCA2)") (class "Default")
      (node (ref "R16") (pin "1") (pinfunction "1_1") (pintype "passive"))
      (node (ref "U3") (pin "6") (pinfunction "OSCA2_6") (pintype "bidirectional"))
    )
    (net (code "26") (name "Net-(U7A--IN)") (class "Default")
      (node (ref "R29") (pin "2") (pinfunction "2_2") (pintype "passive"))
      (node (ref "R31") (pin "1") (pinfunction "1_1") (pintype "passive"))
      (node (ref "U7") (pin "2") (pinfunction "-IN_2") (pintype "input"))
    )
    (net (code "27") (name "Net-(U7B--IN)") (class "Default")
      (node (ref "R23") (pin "1") (pinfunction "1_1") (pintype "passive"))
      (node (ref "R27") (pin "1") (pinfunction "1_1") (pintype "passive"))
      (node (ref "U7") (pin "6") (pinfunction "-IN_6") (pintype "input"))
    )
    (net (code "28") (name "OLED_CS") (class "Default")
      (node (ref "TP24") (pin "TP") (pinfunction "TP_TP") (pintype "input"))
      (node (ref "U3") (pin "26") (pinfunction "CSB_26") (pintype "bidirectional"))
    )
    (net (code "29") (name "OLED_DC") (class "Default")
      (node (ref "TP22") (pin "TP") (pinfunction "TP_TP") (pintype "input"))
      (node (ref "U3") (pin "25") (pinfunction "RS_25") (pintype "bidirectional"))
    )
    (net (code "30") (name "OLED_MOSI") (class "Default")
      (node (ref "TP19") (pin "TP") (pinfunction "TP_TP") (pintype "input"))
      (node (ref "U3") (pin "17") (pinfunction "D16(SDI)_17") (pintype "bidirectional"))
    )
    (net (code "31") (name "OLED_RES") (class "Default")
      (node (ref "TP18") (pin "TP") (pinfunction "TP_TP") (pintype "input"))
      (node (ref "U3") (pin "29") (pinfunction "RESETB_29") (pintype "bidirectional"))
    )
    (net (code "32") (name "OLED_SCLK") (class "Default")
      (node (ref "TP23") (pin "TP") (pinfunction "TP_TP") (pintype "input"))
      (node (ref "U3") (pin "16") (pinfunction "D17(SCLK)_16") (pintype "bidirectional"))
    )
    (net (code "33") (name "PM_NTC") (class "Default")
      (node (ref "R2") (pin "2") (pinfunction "2_2") (pintype "passive"))
      (node (ref "U1") (pin "8") (pinfunction "THERM_8") (pintype "input"))
    )
    (net (code "34") (name "PM_PROG") (class "Default")
      (node (ref "R1") (pin "2") (pinfunction "2_2") (pintype "passive"))
      (node (ref "U1") (pin "6") (pinfunction "PROG_6") (pintype "input"))
    )
    (net (code "35") (name "PM_SHUTDOWN") (class "Default")
      (node (ref "R9") (pin "2") (pinfunction "2_2") (pintype "passive"))
      (node (ref "TP29") (pin "TP") (pinfunction "TP_TP") (pintype "input"))
    )
    (net (code "36") (name "PM_STAT1") (class "Default")
      (node (ref "D1") (pin "C") (pinfunction "C_C") (pintype "passive"))
      (node (ref "U1") (pin "3") (pinfunction "STAT1_3") (pintype "output"))
    )
    (net (code "37") (name "PM_STAT2") (class "Default")
      (node (ref "D2") (pin "C") (pinfunction "C_C") (pintype "passive"))
      (node (ref "U1") (pin "4") (pinfunction "STAT2_4") (pintype "output"))
    )
    (net (code "38") (name "PM_SYSON") (class "Default")
      (node (ref "C12") (pin "1") (pinfunction "P$1_1") (pintype "passive"))
      (node (ref "R10") (pin "2") (pinfunction "2_2") (pintype "passive"))
      (node (ref "U6") (pin "3") (pinfunction "EN_3") (pintype "input"))
    )
    (net (code "39") (name "PM_SYSON_L") (class "Default")
      (node (ref "C11") (pin "1") (pinfunction "P$1_1") (pintype "passive"))
      (node (ref "DZ2") (pin "C") (pinfunction "C_C") (pintype "passive"))
      (node (ref "Q1") (pin "1") (pinfunction "G_1") (pintype "bidirectional"))
      (node (ref "R3") (pin "1") (pinfunction "1_1") (pintype "passive"))
      (node (ref "R8") (pin "1") (pinfunction "1_1") (pintype "passive"))
      (node (ref "S1") (pin "P$2") (pinfunction "P_P$2") (pintype "passive"))
    )
    (net (code "40") (name "PWM0") (class "Default")
      (node (ref "C23") (pin "1") (pinfunction "P$1_1") (pintype "passive"))
      (node (ref "TP12") (pin "TP") (pinfunction "TP_TP") (pintype "input"))
    )
    (net (code "41") (name "VOUTN") (class "Default")
      (node (ref "R23") (pin "2") (pinfunction "2_2") (pintype "passive"))
      (node (ref "R28") (pin "1") (pinfunction "1_1") (pintype "passive"))
      (node (ref "U7") (pin "7") (pinfunction "OUT_7") (pintype "output"))
    )
    (net (code "42") (name "VOUTN_R") (class "Default")
      (node (ref "CN1") (pin "1") (pinfunction "1_1") (pintype "passive"))
      (node (ref "R28") (pin "2") (pinfunction "2_2") (pintype "passive"))
    )
    (net (code "43") (name "VOUTP") (class "Default")
      (node (ref "R24") (pin "1") (pinfunction "1_1") (pintype "passive"))
      (node (ref "R27") (pin "2") (pinfunction "2_2") (pintype "passive"))
      (node (ref "R31") (pin "2") (pinfunction "2_2") (pintype "passive"))
      (node (ref "U7") (pin "1") (pinfunction "OUT_1") (pintype "output"))
    )
    (net (code "44") (name "VOUTP_R") (class "Default")
      (node (ref "CN1") (pin "2") (pinfunction "2_2") (pintype "passive"))
      (node (ref "R24") (pin "2") (pinfunction "2_2") (pintype "passive"))
    )
    (net (code "45") (name "VSYS") (class "Default")
      (node (ref "C3") (pin "1") (pinfunction "P$1_1") (pintype "passive"))
      (node (ref "R17") (pin "2") (pinfunction "2_2") (pintype "passive"))
      (node (ref "R30") (pin "2") (pinfunction "2_2") (pintype "passive"))
      (node (ref "R7") (pin "2") (pinfunction "2_2") (pintype "passive"))
      (node (ref "U6") (pin "1") (pinfunction "VOUT_1") (pintype "power_in"))
    )
    (net (code "46") (name "VSYS_AMP") (class "Default")
      (node (ref "C20") (pin "2") (pinfunction "P$2_2") (pintype "passive"))
      (node (ref "R20") (pin "2") (pinfunction "2_2") (pintype "passive"))
      (node (ref "R26") (pin "2") (pinfunction "2_2") (pintype "passive"))
      (node (ref "U7") (pin "8") (pinfunction "V+_8") (pintype "power_in"))
    )
    (net (code "47") (name "VSYS_LCD") (class "Default")
      (node (ref "C4") (pin "1") (pinfunction "P$1_1") (pintype "passive"))
      (node (ref "L1") (pin "P$1") (pinfunction "1_P$1") (pintype "passive"))
      (node (ref "R17") (pin "1") (pinfunction "1_1") (pintype "passive"))
      (node (ref "U2") (pin "4") (pinfunction "EN_4") (pintype "input"))
      (node (ref "U2") (pin "6") (pinfunction "VIN_6") (pintype "power_in"))
    )
    (net (code "48") (name "VSYS_RPI") (class "Default")
      (node (ref "R30") (pin "1") (pinfunction "1_1") (pintype "passive"))
      (node (ref "TP2") (pin "TP") (pinfunction "TP_TP") (pintype "input"))
      (node (ref "TP4") (pin "TP") (pinfunction "TP_TP") (pintype "input"))
    )
    (net (code "49") (name "V_AMP_CM") (class "Default")
      (node (ref "C22") (pin "2") (pinfunction "P$2_2") (pintype "passive"))
      (node (ref "R20") (pin "1") (pinfunction "1_1") (pintype "passive"))
      (node (ref "R21") (pin "2") (pinfunction "2_2") (pintype "passive"))
      (node (ref "R22") (pin "2") (pinfunction "2_2") (pintype "passive"))
      (node (ref "U7") (pin "5") (pinfunction "+IN_5") (pintype "input"))
    )
    (net (code "50") (name "V_BATT") (class "Default")
      (node (ref "C1") (pin "1") (pinfunction "P$1_1") (pintype "passive"))
      (node (ref "CN2") (pin "1") (pinfunction "2_1") (pintype "passive"))
      (node (ref "Q1") (pin "2") (pinfunction "S_2") (pintype "bidirectional"))
      (node (ref "R3") (pin "2") (pinfunction "2_2") (pintype "passive"))
      (node (ref "R5") (pin "2") (pinfunction "2_2") (pintype "passive"))
      (node (ref "R6") (pin "2") (pinfunction "2_2") (pintype "passive"))
      (node (ref "U1") (pin "10") (pinfunction "VBAT_10") (pintype "power_in"))
      (node (ref "U1") (pin "9") (pinfunction "VBAT_9") (pintype "power_in"))
      (node (ref "U6") (pin "4") (pinfunction "VIN_4") (pintype "power_in"))
    )
    (net (code "51") (name "V_USB") (class "Default")
      (node (ref "C2") (pin "1") (pinfunction "P$1_1") (pintype "passive"))
      (node (ref "DZ1") (pin "C") (pinfunction "C_C") (pintype "passive"))
      (node (ref "J1") (pin "VBUS") (pinfunction "VBUS_VBUS") (pintype "power_in"))
      (node (ref "U1") (pin "1") (pinfunction "VDD_1") (pintype "power_in"))
      (node (ref "U1") (pin "2") (pinfunction "VDD_2") (pintype "power_in"))
    )
    (net (code "52") (name "unconnected-(J1-PadD+)") (class "Default")
      (node (ref "J1") (pin "D+") (pinfunction "D+_D+") (pintype "bidirectional"))
    )
    (net (code "53") (name "unconnected-(J1-PadD-)") (class "Default")
      (node (ref "J1") (pin "D-") (pinfunction "D-_D-") (pintype "bidirectional"))
    )
    (net (code "54") (name "unconnected-(J1-PadID)") (class "Default")
      (node (ref "J1") (pin "ID") (pinfunction "ID_ID") (pintype "bidirectional"))
    )
    (net (code "55") (name "unconnected-(S1-O-PadP$1)") (class "Default")
      (node (ref "S1") (pin "P$1") (pinfunction "O_P$1") (pintype "passive"))
    )
    (net (code "56") (name "unconnected-(U1-~{PG}-Pad7)") (class "Default")
      (node (ref "U1") (pin "7") (pinfunction "~{PG}_7") (pintype "output"))
    )
    (net (code "57") (name "unconnected-(U3-CPU-Pad14)") (class "Default")
      (node (ref "U3") (pin "14") (pinfunction "CPU_14") (pintype "bidirectional"))
    )
    (net (code "58") (name "unconnected-(U3-D10-Pad23)") (class "Default")
      (node (ref "U3") (pin "23") (pinfunction "D10_23") (pintype "bidirectional"))
    )
    (net (code "59") (name "unconnected-(U3-D11-Pad22)") (class "Default")
      (node (ref "U3") (pin "22") (pinfunction "D11_22") (pintype "bidirectional"))
    )
    (net (code "60") (name "unconnected-(U3-D12-Pad21)") (class "Default")
      (node (ref "U3") (pin "21") (pinfunction "D12_21") (pintype "bidirectional"))
    )
    (net (code "61") (name "unconnected-(U3-D13-Pad20)") (class "Default")
      (node (ref "U3") (pin "20") (pinfunction "D13_20") (pintype "bidirectional"))
    )
    (net (code "62") (name "unconnected-(U3-D14-Pad19)") (class "Default")
      (node (ref "U3") (pin "19") (pinfunction "D14_19") (pintype "bidirectional"))
    )
    (net (code "63") (name "unconnected-(U3-D15(SDO)-Pad18)") (class "Default")
      (node (ref "U3") (pin "18") (pinfunction "D15(SDO)_18") (pintype "bidirectional"))
    )
    (net (code "64") (name "unconnected-(U3-DOTCLK-Pad12)") (class "Default")
      (node (ref "U3") (pin "12") (pinfunction "DOTCLK_12") (pintype "bidirectional"))
    )
    (net (code "65") (name "unconnected-(U3-ENABLE-Pad13)") (class "Default")
      (node (ref "U3") (pin "13") (pinfunction "ENABLE_13") (pintype "bidirectional"))
    )
    (net (code "66") (name "unconnected-(U3-HSYNC-Pad11)") (class "Default")
      (node (ref "U3") (pin "11") (pinfunction "HSYNC_11") (pintype "bidirectional"))
    )
    (net (code "67") (name "unconnected-(U3-NC(GND)-Pad1)") (class "Default")
      (node (ref "U3") (pin "1") (pinfunction "NC(GND)_1") (pintype "no_connect"))
    )
    (net (code "68") (name "unconnected-(U3-NC(GND)-Pad35)") (class "Default")
      (node (ref "U3") (pin "35") (pinfunction "NC(GND)_35") (pintype "no_connect"))
    )
    (net (code "69") (name "unconnected-(U3-VSYNC-Pad10)") (class "Default")
      (node (ref "U3") (pin "10") (pinfunction "VSYNC_10") (pintype "bidirectional"))
    )
    (net (code "70") (name "unconnected-(U3-VSYNCO-Pad9)") (class "Default")
      (node (ref "U3") (pin "9") (pinfunction "VSYNCO_9") (pintype "output"))
    )
    (net (code "71") (name "unconnected-(U6-NC-Pad6)") (class "Default")
      (node (ref "U6") (pin "6") (pinfunction "NC_6") (pintype "no_connect"))
    )
  )
)
